# tm7_revC.net
KiCad netlist of a schematic drawn in EAGLE
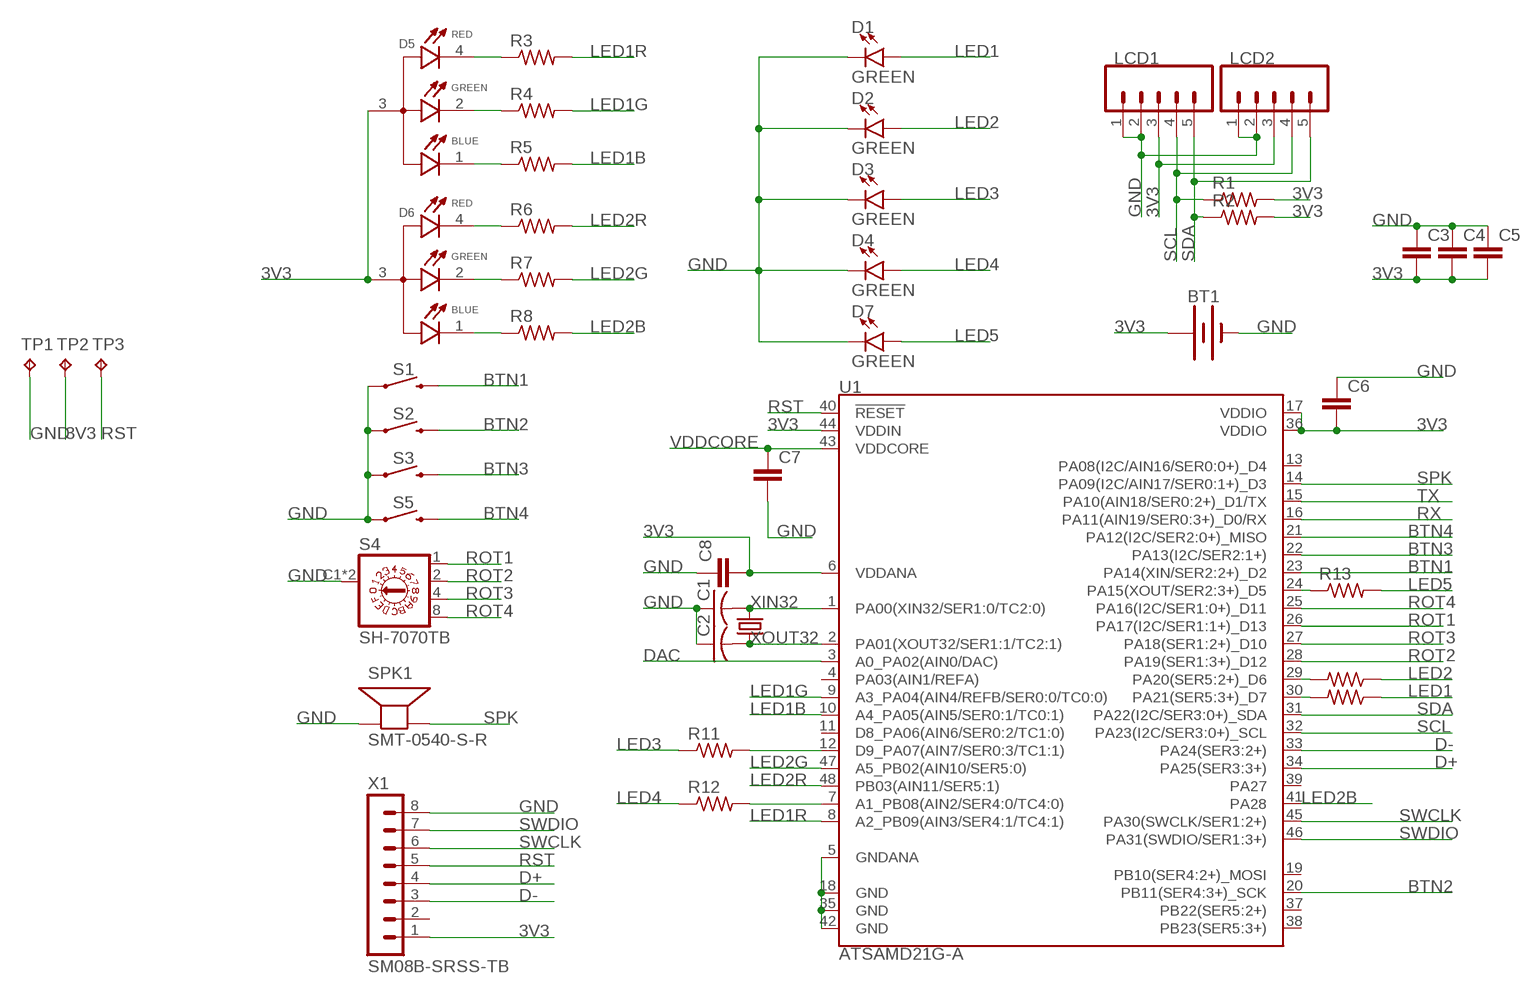
[diagram p0: schematic, sheet 1]

(export (version "E")
  (design (tool "Eeschema 10.0.6"))
  (components
    (comp (ref "BT1")
      (value "BATTERY-20MM_SMD_4LEGS_OVERPASTE_INNER")
      (footprint "eagle-import:BATTCON_20MM_4LEGS_OVERPASTE_INNER")
      (libsource (lib "eagle-import") (part "BATTERY-20MM_SMD_4LEGS_OVERPASTE_INNER"))
    )
    (comp (ref "C1")
      (value "C-USC0603")
      (footprint "eagle-import:C0603")
      (libsource (lib "eagle-import") (part "C-USC0603"))
    )
    (comp (ref "C2")
      (value "C-USC0603")
      (footprint "eagle-import:C0603")
      (libsource (lib "eagle-import") (part "C-USC0603"))
    )
    (comp (ref "C3")
      (value "C-EUC0603")
      (footprint "eagle-import:C0603")
      (libsource (lib "eagle-import") (part "C-EUC0603"))
    )
    (comp (ref "C4")
      (value "C-EUC0603")
      (footprint "eagle-import:C0603")
      (libsource (lib "eagle-import") (part "C-EUC0603"))
    )
    (comp (ref "C5")
      (value "C-EUC0603")
      (footprint "eagle-import:C0603")
      (libsource (lib "eagle-import") (part "C-EUC0603"))
    )
    (comp (ref "C6")
      (value "C-EUC0603")
      (footprint "eagle-import:C0603")
      (libsource (lib "eagle-import") (part "C-EUC0603"))
    )
    (comp (ref "C7")
      (value "C-EUC0603")
      (footprint "eagle-import:C0603")
      (libsource (lib "eagle-import") (part "C-EUC0603"))
    )
    (comp (ref "C8")
      (value "C-EUC0603")
      (footprint "eagle-import:C0603")
      (libsource (lib "eagle-import") (part "C-EUC0603"))
    )
    (comp (ref "D1")
      (value "GREEN")
      (footprint "eagle-import:LED-1206")
      (libsource (lib "eagle-import") (part "LED-GREEN1206"))
    )
    (comp (ref "D2")
      (value "GREEN")
      (footprint "eagle-import:LED-1206")
      (libsource (lib "eagle-import") (part "LED-GREEN1206"))
    )
    (comp (ref "D3")
      (value "GREEN")
      (footprint "eagle-import:LED-1206")
      (libsource (lib "eagle-import") (part "LED-GREEN1206"))
    )
    (comp (ref "D4")
      (value "GREEN")
      (footprint "eagle-import:LED-1206")
      (libsource (lib "eagle-import") (part "LED-GREEN1206"))
    )
    (comp (ref "D5")
      (value "EAST1616RGBA3")
      (footprint "eagle-import:LED_EAST1616RGBA3")
      (fields (field (name "MF") "Everlight Electronics"))
      (libsource (lib "eagle-import") (part "EAST1616RGBA3"))
    )
    (comp (ref "D6")
      (value "EAST1616RGBA3")
      (footprint "eagle-import:LED_EAST1616RGBA3")
      (fields (field (name "MF") "Everlight Electronics"))
      (libsource (lib "eagle-import") (part "EAST1616RGBA3"))
    )
    (comp (ref "D7")
      (value "GREEN")
      (footprint "eagle-import:LED-1206")
      (libsource (lib "eagle-import") (part "LED-GREEN1206"))
    )
    (comp (ref "LCD1")
      (value "CONN_05VERT_FEMALE_HEADER")
      (footprint "eagle-import:1X05_SMD_VERTICAL_COMBO")
      (libsource (lib "eagle-import") (part "CONN_05VERT_FEMALE_HEADER"))
    )
    (comp (ref "LCD2")
      (value "CONN_05VERT_FEMALE_HEADER")
      (footprint "eagle-import:1X05_SMD_VERTICAL_COMBO")
      (libsource (lib "eagle-import") (part "CONN_05VERT_FEMALE_HEADER"))
    )
    (comp (ref "R1")
      (value "R-US_R0603")
      (footprint "eagle-import:R0603")
      (libsource (lib "eagle-import") (part "R-US_R0603"))
    )
    (comp (ref "R2")
      (value "R-US_R0603")
      (footprint "eagle-import:R0603")
      (libsource (lib "eagle-import") (part "R-US_R0603"))
    )
    (comp (ref "R3")
      (value "R-US_R0603")
      (footprint "eagle-import:R0603")
      (libsource (lib "eagle-import") (part "R-US_R0603"))
    )
    (comp (ref "R4")
      (value "R-US_R0603")
      (footprint "eagle-import:R0603")
      (libsource (lib "eagle-import") (part "R-US_R0603"))
    )
    (comp (ref "R5")
      (value "R-US_R0603")
      (footprint "eagle-import:R0603")
      (libsource (lib "eagle-import") (part "R-US_R0603"))
    )
    (comp (ref "R6")
      (value "R-US_R0603")
      (footprint "eagle-import:R0603")
      (libsource (lib "eagle-import") (part "R-US_R0603"))
    )
    (comp (ref "R7")
      (value "R-US_R0603")
      (footprint "eagle-import:R0603")
      (libsource (lib "eagle-import") (part "R-US_R0603"))
    )
    (comp (ref "R8")
      (value "R-US_R0603")
      (footprint "eagle-import:R0603")
      (libsource (lib "eagle-import") (part "R-US_R0603"))
    )
    (comp (ref "R9")
      (value "R-US_R0603")
      (footprint "eagle-import:R0603")
      (libsource (lib "eagle-import") (part "R-US_R0603"))
    )
    (comp (ref "R10")
      (value "R-US_R0603")
      (footprint "eagle-import:R0603")
      (libsource (lib "eagle-import") (part "R-US_R0603"))
    )
    (comp (ref "R11")
      (value "R-US_R0603")
      (footprint "eagle-import:R0603")
      (libsource (lib "eagle-import") (part "R-US_R0603"))
    )
    (comp (ref "R12")
      (value "R-US_R0603")
      (footprint "eagle-import:R0603")
      (libsource (lib "eagle-import") (part "R-US_R0603"))
    )
    (comp (ref "R13")
      (value "R-US_R0603")
      (footprint "eagle-import:R0603")
      (libsource (lib "eagle-import") (part "R-US_R0603"))
    )
    (comp (ref "S1")
      (value "MOMENTARY-SWITCH-SPST-SMD-6.0X3.5MM")
      (footprint "eagle-import:TACTILE_SWITCH_SMD_6.0X3.5MM")
      (libsource (lib "eagle-import") (part "MOMENTARY-SWITCH-SPST-SMD-6.0X3.5MM"))
    )
    (comp (ref "S2")
      (value "MOMENTARY-SWITCH-SPST-SMD-6.0X3.5MM")
      (footprint "eagle-import:TACTILE_SWITCH_SMD_6.0X3.5MM")
      (libsource (lib "eagle-import") (part "MOMENTARY-SWITCH-SPST-SMD-6.0X3.5MM"))
    )
    (comp (ref "S3")
      (value "MOMENTARY-SWITCH-SPST-SMD-6.0X3.5MM")
      (footprint "eagle-import:TACTILE_SWITCH_SMD_6.0X3.5MM")
      (libsource (lib "eagle-import") (part "MOMENTARY-SWITCH-SPST-SMD-6.0X3.5MM"))
    )
    (comp (ref "S4")
      (value "SH-7070TB")
      (footprint "eagle-import:SH-7070B")
      (fields (field (name "MF") "Nidec Copal"))
      (libsource (lib "eagle-import") (part "SH-7070TB"))
    )
    (comp (ref "S5")
      (value "MOMENTARY-SWITCH-SPST-SMD-6.0X3.5MM")
      (footprint "eagle-import:TACTILE_SWITCH_SMD_6.0X3.5MM")
      (libsource (lib "eagle-import") (part "MOMENTARY-SWITCH-SPST-SMD-6.0X3.5MM"))
    )
    (comp (ref "SPK1")
      (value "SMT-0540-S-R")
      (footprint "eagle-import:SMT-0540-S-R")
      (fields (field (name "MF") "PUI"))
      (libsource (lib "eagle-import") (part "SMT-0540-S-R"))
    )
    (comp (ref "TP1")
      (value "TPTP12R")
      (footprint "eagle-import:TP12R")
      (libsource (lib "eagle-import") (part "TPTP12R"))
    )
    (comp (ref "TP2")
      (value "TPTP12R")
      (footprint "eagle-import:TP12R")
      (libsource (lib "eagle-import") (part "TPTP12R"))
    )
    (comp (ref "TP3")
      (value "TPTP12R")
      (footprint "eagle-import:TP12R")
      (libsource (lib "eagle-import") (part "TPTP12R"))
    )
    (comp (ref "U1")
      (value "ATSAMD21G-A")
      (footprint "eagle-import:TQFP-48")
      (libsource (lib "eagle-import") (part "ATSAMD21G-A"))
    )
    (comp (ref "X1")
      (value "SM08B-SRSS-TB")
      (footprint "eagle-import:SM08B-SRSS-TB")
      (libsource (lib "eagle-import") (part "SM08B-SRSS-TB"))
    )
    (comp (ref "Y1")
      (value "32.768kHz")
      (footprint "eagle-import:CRYSTAL-SMD-3.2X1.5MM")
      (libsource (lib "eagle-import") (part "CRYSTAL-32.768KHZSMD-3.2X1.5"))
    )
  )
  (nets
    (net (code "1") (name "/3V3") (class "Default")
      (node (ref "BT1") (pin "1") (pinfunction "+_1") (pintype "power_in"))
      (node (ref "C3") (pin "2") (pinfunction "2_2") (pintype "passive"))
      (node (ref "C4") (pin "2") (pinfunction "2_2") (pintype "passive"))
      (node (ref "C5") (pin "2") (pinfunction "2_2") (pintype "passive"))
      (node (ref "C6") (pin "2") (pinfunction "2_2") (pintype "passive"))
      (node (ref "C8") (pin "2") (pinfunction "2_2") (pintype "passive"))
      (node (ref "D5") (pin "3") (pinfunction "A_3") (pintype "passive"))
      (node (ref "D6") (pin "3") (pinfunction "A_3") (pintype "passive"))
      (node (ref "LCD1") (pin "3") (pinfunction "3_3") (pintype "passive"))
      (node (ref "LCD2") (pin "3") (pinfunction "3_3") (pintype "passive"))
      (node (ref "R1") (pin "2") (pinfunction "2_2") (pintype "passive"))
      (node (ref "R2") (pin "2") (pinfunction "2_2") (pintype "passive"))
      (node (ref "TP2") (pin "TP") (pinfunction "TP_TP") (pintype "input"))
      (node (ref "U1") (pin "17") (pinfunction "VDDIO_17") (pintype "bidirectional"))
      (node (ref "U1") (pin "36") (pinfunction "VDDIO_36") (pintype "bidirectional"))
      (node (ref "U1") (pin "44") (pinfunction "VDDIN_44") (pintype "bidirectional"))
      (node (ref "U1") (pin "6") (pinfunction "VDDANA_6") (pintype "bidirectional"))
      (node (ref "X1") (pin "1") (pinfunction "1_1") (pintype "passive"))
    )
    (net (code "2") (name "/BTN1") (class "Default")
      (node (ref "S1") (pin "2") (pinfunction "2_2") (pintype "passive"))
      (node (ref "U1") (pin "23") (pinfunction "PA14(XIN/SER2:2+)_D2_23") (pintype "bidirectional"))
    )
    (net (code "3") (name "/BTN2") (class "Default")
      (node (ref "S2") (pin "2") (pinfunction "2_2") (pintype "passive"))
      (node (ref "U1") (pin "20") (pinfunction "PB11(SER4:3+)_SCK_20") (pintype "bidirectional"))
    )
    (net (code "4") (name "/BTN3") (class "Default")
      (node (ref "S3") (pin "2") (pinfunction "2_2") (pintype "passive"))
      (node (ref "U1") (pin "22") (pinfunction "PA13(I2C/SER2:1+)_22") (pintype "bidirectional"))
    )
    (net (code "5") (name "/BTN4") (class "Default")
      (node (ref "S5") (pin "2") (pinfunction "2_2") (pintype "passive"))
      (node (ref "U1") (pin "21") (pinfunction "PA12(I2C/SER2:0+)_MISO_21") (pintype "bidirectional"))
    )
    (net (code "6") (name "/D+") (class "Default")
      (node (ref "U1") (pin "34") (pinfunction "PA25(SER3:3+)_34") (pintype "bidirectional"))
      (node (ref "X1") (pin "4") (pinfunction "4_4") (pintype "passive"))
    )
    (net (code "7") (name "/D-") (class "Default")
      (node (ref "U1") (pin "33") (pinfunction "PA24(SER3:2+)_33") (pintype "bidirectional"))
      (node (ref "X1") (pin "3") (pinfunction "3_3") (pintype "passive"))
    )
    (net (code "8") (name "/DAC") (class "Default")
      (node (ref "U1") (pin "3") (pinfunction "A0_PA02(AIN0/DAC)_3") (pintype "bidirectional"))
    )
    (net (code "9") (name "/GND") (class "Default")
      (node (ref "BT1") (pin "2") (pinfunction "-_2") (pintype "power_in"))
      (node (ref "C1") (pin "1") (pinfunction "1_1") (pintype "passive"))
      (node (ref "C2") (pin "1") (pinfunction "1_1") (pintype "passive"))
      (node (ref "C3") (pin "1") (pinfunction "1_1") (pintype "passive"))
      (node (ref "C4") (pin "1") (pinfunction "1_1") (pintype "passive"))
      (node (ref "C5") (pin "1") (pinfunction "1_1") (pintype "passive"))
      (node (ref "C6") (pin "1") (pinfunction "1_1") (pintype "passive"))
      (node (ref "C7") (pin "2") (pinfunction "2_2") (pintype "passive"))
      (node (ref "C8") (pin "1") (pinfunction "1_1") (pintype "passive"))
      (node (ref "D1") (pin "C") (pinfunction "C_C") (pintype "passive"))
      (node (ref "D2") (pin "C") (pinfunction "C_C") (pintype "passive"))
      (node (ref "D3") (pin "C") (pinfunction "C_C") (pintype "passive"))
      (node (ref "D4") (pin "C") (pinfunction "C_C") (pintype "passive"))
      (node (ref "D7") (pin "C") (pinfunction "C_C") (pintype "passive"))
      (node (ref "LCD1") (pin "1") (pinfunction "1_1") (pintype "passive"))
      (node (ref "LCD1") (pin "2") (pinfunction "2_2") (pintype "passive"))
      (node (ref "LCD2") (pin "1") (pinfunction "1_1") (pintype "passive"))
      (node (ref "LCD2") (pin "2") (pinfunction "2_2") (pintype "passive"))
      (node (ref "S1") (pin "1") (pinfunction "1_1") (pintype "passive"))
      (node (ref "S2") (pin "1") (pinfunction "1_1") (pintype "passive"))
      (node (ref "S3") (pin "1") (pinfunction "1_1") (pintype "passive"))
      (node (ref "S4") (pin "C1") (pinfunction "C_C1") (pintype "passive"))
      (node (ref "S4") (pin "C2") (pinfunction "C_C2") (pintype "passive"))
      (node (ref "S5") (pin "1") (pinfunction "1_1") (pintype "passive"))
      (node (ref "SPK1") (pin "-") (pinfunction "+_-") (pintype "passive"))
      (node (ref "TP1") (pin "TP") (pinfunction "TP_TP") (pintype "input"))
      (node (ref "U1") (pin "18") (pinfunction "GND_18") (pintype "bidirectional"))
      (node (ref "U1") (pin "35") (pinfunction "GND_35") (pintype "bidirectional"))
      (node (ref "U1") (pin "42") (pinfunction "GND_42") (pintype "bidirectional"))
      (node (ref "U1") (pin "5") (pinfunction "GNDANA_5") (pintype "bidirectional"))
      (node (ref "X1") (pin "8") (pinfunction "8_8") (pintype "passive"))
    )
    (net (code "10") (name "/LED1") (class "Default")
      (node (ref "D1") (pin "A") (pinfunction "A_A") (pintype "passive"))
      (node (ref "R9") (pin "1") (pinfunction "1_1") (pintype "passive"))
    )
    (net (code "11") (name "/LED1B") (class "Default")
      (node (ref "R5") (pin "2") (pinfunction "2_2") (pintype "passive"))
      (node (ref "U1") (pin "10") (pinfunction "A4_PA05(AIN5/SER0:1/TC0:1)_10") (pintype "bidirectional"))
    )
    (net (code "12") (name "/LED1G") (class "Default")
      (node (ref "R4") (pin "2") (pinfunction "2_2") (pintype "passive"))
      (node (ref "U1") (pin "9") (pinfunction "A3_PA04(AIN4/REFB/SER0:0/TC0:0)_9") (pintype "bidirectional"))
    )
    (net (code "13") (name "/LED1R") (class "Default")
      (node (ref "R3") (pin "2") (pinfunction "2_2") (pintype "passive"))
      (node (ref "U1") (pin "8") (pinfunction "A2_PB09(AIN3/SER4:1/TC4:1)_8") (pintype "bidirectional"))
    )
    (net (code "14") (name "/LED2") (class "Default")
      (node (ref "D2") (pin "A") (pinfunction "A_A") (pintype "passive"))
      (node (ref "R10") (pin "1") (pinfunction "1_1") (pintype "passive"))
    )
    (net (code "15") (name "/LED2B") (class "Default")
      (node (ref "R8") (pin "2") (pinfunction "2_2") (pintype "passive"))
      (node (ref "U1") (pin "41") (pinfunction "PA28_41") (pintype "bidirectional"))
    )
    (net (code "16") (name "/LED2G") (class "Default")
      (node (ref "R7") (pin "2") (pinfunction "2_2") (pintype "passive"))
      (node (ref "U1") (pin "47") (pinfunction "A5_PB02(AIN10/SER5:0)_47") (pintype "bidirectional"))
    )
    (net (code "17") (name "/LED2R") (class "Default")
      (node (ref "R6") (pin "2") (pinfunction "2_2") (pintype "passive"))
      (node (ref "U1") (pin "48") (pinfunction "PB03(AIN11/SER5:1)_48") (pintype "bidirectional"))
    )
    (net (code "18") (name "/LED3") (class "Default")
      (node (ref "D3") (pin "A") (pinfunction "A_A") (pintype "passive"))
      (node (ref "R11") (pin "1") (pinfunction "1_1") (pintype "passive"))
    )
    (net (code "19") (name "/LED4") (class "Default")
      (node (ref "D4") (pin "A") (pinfunction "A_A") (pintype "passive"))
      (node (ref "R12") (pin "1") (pinfunction "1_1") (pintype "passive"))
    )
    (net (code "20") (name "/LED5") (class "Default")
      (node (ref "D7") (pin "A") (pinfunction "A_A") (pintype "passive"))
      (node (ref "R13") (pin "2") (pinfunction "2_2") (pintype "passive"))
    )
    (net (code "21") (name "/ROT1") (class "Default")
      (node (ref "S4") (pin "1") (pinfunction "1_1") (pintype "passive"))
      (node (ref "U1") (pin "26") (pinfunction "PA17(I2C/SER1:1+)_D13_26") (pintype "bidirectional"))
    )
    (net (code "22") (name "/ROT2") (class "Default")
      (node (ref "S4") (pin "2") (pinfunction "2_2") (pintype "passive"))
      (node (ref "U1") (pin "28") (pinfunction "PA19(SER1:3+)_D12_28") (pintype "bidirectional"))
    )
    (net (code "23") (name "/ROT3") (class "Default")
      (node (ref "S4") (pin "4") (pinfunction "4_4") (pintype "passive"))
      (node (ref "U1") (pin "27") (pinfunction "PA18(SER1:2+)_D10_27") (pintype "bidirectional"))
    )
    (net (code "24") (name "/ROT4") (class "Default")
      (node (ref "S4") (pin "8") (pinfunction "8_8") (pintype "passive"))
      (node (ref "U1") (pin "25") (pinfunction "PA16(I2C/SER1:0+)_D11_25") (pintype "bidirectional"))
    )
    (net (code "25") (name "/RST") (class "Default")
      (node (ref "TP3") (pin "TP") (pinfunction "TP_TP") (pintype "input"))
      (node (ref "U1") (pin "40") (pinfunction "~{RESET}_40") (pintype "bidirectional"))
      (node (ref "X1") (pin "5") (pinfunction "5_5") (pintype "passive"))
    )
    (net (code "26") (name "/RX") (class "Default")
      (node (ref "U1") (pin "16") (pinfunction "PA11(AIN19/SER0:3+)_D0/RX_16") (pintype "bidirectional"))
    )
    (net (code "27") (name "/SCL") (class "Default")
      (node (ref "LCD1") (pin "4") (pinfunction "4_4") (pintype "passive"))
      (node (ref "LCD2") (pin "4") (pinfunction "4_4") (pintype "passive"))
      (node (ref "R1") (pin "1") (pinfunction "1_1") (pintype "passive"))
      (node (ref "U1") (pin "32") (pinfunction "PA23(I2C/SER3:0+)_SCL_32") (pintype "bidirectional"))
    )
    (net (code "28") (name "/SDA") (class "Default")
      (node (ref "LCD1") (pin "5") (pinfunction "5_5") (pintype "passive"))
      (node (ref "LCD2") (pin "5") (pinfunction "5_5") (pintype "passive"))
      (node (ref "R2") (pin "1") (pinfunction "1_1") (pintype "passive"))
      (node (ref "U1") (pin "31") (pinfunction "PA22(I2C/SER3:0+)_SDA_31") (pintype "bidirectional"))
    )
    (net (code "29") (name "/SPK") (class "Default")
      (node (ref "SPK1") (pin "+") (pinfunction "-_+") (pintype "passive"))
      (node (ref "U1") (pin "14") (pinfunction "PA09(I2C/AIN17/SER0:1+)_D3_14") (pintype "bidirectional"))
    )
    (net (code "30") (name "/SWCLK") (class "Default")
      (node (ref "U1") (pin "45") (pinfunction "PA30(SWCLK/SER1:2+)_45") (pintype "bidirectional"))
      (node (ref "X1") (pin "6") (pinfunction "6_6") (pintype "passive"))
    )
    (net (code "31") (name "/SWDIO") (class "Default")
      (node (ref "U1") (pin "46") (pinfunction "PA31(SWDIO/SER1:3+)_46") (pintype "bidirectional"))
      (node (ref "X1") (pin "7") (pinfunction "7_7") (pintype "passive"))
    )
    (net (code "32") (name "/TX") (class "Default")
      (node (ref "U1") (pin "15") (pinfunction "PA10(AIN18/SER0:2+)_D1/TX_15") (pintype "bidirectional"))
    )
    (net (code "33") (name "/VDDCORE") (class "Default")
      (node (ref "C7") (pin "1") (pinfunction "1_1") (pintype "passive"))
      (node (ref "U1") (pin "43") (pinfunction "VDDCORE_43") (pintype "bidirectional"))
    )
    (net (code "34") (name "/XIN32") (class "Default")
      (node (ref "C1") (pin "2") (pinfunction "2_2") (pintype "passive"))
      (node (ref "U1") (pin "1") (pinfunction "PA00(XIN32/SER1:0/TC2:0)_1") (pintype "bidirectional"))
      (node (ref "Y1") (pin "P$2") (pinfunction "2_P$2") (pintype "passive"))
    )
    (net (code "35") (name "/XOUT32") (class "Default")
      (node (ref "C2") (pin "2") (pinfunction "2_2") (pintype "passive"))
      (node (ref "U1") (pin "2") (pinfunction "PA01(XOUT32/SER1:1/TC2:1)_2") (pintype "bidirectional"))
      (node (ref "Y1") (pin "P$1") (pinfunction "1_P$1") (pintype "passive"))
    )
    (net (code "36") (name "Net-(D5-B_C)") (class "Default")
      (node (ref "D5") (pin "1") (pinfunction "B_C_1") (pintype "passive"))
      (node (ref "R5") (pin "1") (pinfunction "1_1") (pintype "passive"))
    )
    (net (code "37") (name "Net-(D5-G_C)") (class "Default")
      (node (ref "D5") (pin "2") (pinfunction "G_C_2") (pintype "passive"))
      (node (ref "R4") (pin "1") (pinfunction "1_1") (pintype "passive"))
    )
    (net (code "38") (name "Net-(D5-R_C)") (class "Default")
      (node (ref "D5") (pin "4") (pinfunction "R_C_4") (pintype "passive"))
      (node (ref "R3") (pin "1") (pinfunction "1_1") (pintype "passive"))
    )
    (net (code "39") (name "Net-(D6-B_C)") (class "Default")
      (node (ref "D6") (pin "1") (pinfunction "B_C_1") (pintype "passive"))
      (node (ref "R8") (pin "1") (pinfunction "1_1") (pintype "passive"))
    )
    (net (code "40") (name "Net-(D6-G_C)") (class "Default")
      (node (ref "D6") (pin "2") (pinfunction "G_C_2") (pintype "passive"))
      (node (ref "R7") (pin "1") (pinfunction "1_1") (pintype "passive"))
    )
    (net (code "41") (name "Net-(D6-R_C)") (class "Default")
      (node (ref "D6") (pin "4") (pinfunction "R_C_4") (pintype "passive"))
      (node (ref "R6") (pin "1") (pinfunction "1_1") (pintype "passive"))
    )
    (net (code "42") (name "Net-(U1-A1_PB08(AIN2{slash}SER4:0{slash}TC4:0))") (class "Default")
      (node (ref "R12") (pin "2") (pinfunction "2_2") (pintype "passive"))
      (node (ref "U1") (pin "7") (pinfunction "A1_PB08(AIN2/SER4:0/TC4:0)_7") (pintype "bidirectional"))
    )
    (net (code "43") (name "Net-(U1-D9_PA07(AIN7{slash}SER0:3{slash}TC1:1))") (class "Default")
      (node (ref "R11") (pin "2") (pinfunction "2_2") (pintype "passive"))
      (node (ref "U1") (pin "12") (pinfunction "D9_PA07(AIN7/SER0:3/TC1:1)_12") (pintype "bidirectional"))
    )
    (net (code "44") (name "Net-(U1-PA15(XOUT{slash}SER2:3+)_D5)") (class "Default")
      (node (ref "R13") (pin "1") (pinfunction "1_1") (pintype "passive"))
      (node (ref "U1") (pin "24") (pinfunction "PA15(XOUT/SER2:3+)_D5_24") (pintype "bidirectional"))
    )
    (net (code "45") (name "Net-(U1-PA20(SER5:2+)_D6)") (class "Default")
      (node (ref "R10") (pin "2") (pinfunction "2_2") (pintype "passive"))
      (node (ref "U1") (pin "29") (pinfunction "PA20(SER5:2+)_D6_29") (pintype "bidirectional"))
    )
    (net (code "46") (name "Net-(U1-PA21(SER5:3+)_D7)") (class "Default")
      (node (ref "R9") (pin "2") (pinfunction "2_2") (pintype "passive"))
      (node (ref "U1") (pin "30") (pinfunction "PA21(SER5:3+)_D7_30") (pintype "bidirectional"))
    )
    (net (code "47") (name "unconnected-(U1-D8_PA06(AIN6{slash}SER0:2{slash}TC1:0)-Pad11)") (class "Default")
      (node (ref "U1") (pin "11") (pinfunction "D8_PA06(AIN6/SER0:2/TC1:0)_11") (pintype "bidirectional"))
    )
    (net (code "48") (name "unconnected-(U1-PA03(AIN1{slash}REFA)-Pad4)") (class "Default")
      (node (ref "U1") (pin "4") (pinfunction "PA03(AIN1/REFA)_4") (pintype "bidirectional"))
    )
    (net (code "49") (name "unconnected-(U1-PA08(I2C{slash}AIN16{slash}SER0:0+)_D4-Pad13)") (class "Default")
      (node (ref "U1") (pin "13") (pinfunction "PA08(I2C/AIN16/SER0:0+)_D4_13") (pintype "bidirectional"))
    )
    (net (code "50") (name "unconnected-(U1-PA27-Pad39)") (class "Default")
      (node (ref "U1") (pin "39") (pinfunction "PA27_39") (pintype "bidirectional"))
    )
    (net (code "51") (name "unconnected-(U1-PB10(SER4:2+)_MOSI-Pad19)") (class "Default")
      (node (ref "U1") (pin "19") (pinfunction "PB10(SER4:2+)_MOSI_19") (pintype "bidirectional"))
    )
    (net (code "52") (name "unconnected-(U1-PB22(SER5:2+)-Pad37)") (class "Default")
      (node (ref "U1") (pin "37") (pinfunction "PB22(SER5:2+)_37") (pintype "bidirectional"))
    )
    (net (code "53") (name "unconnected-(U1-PB23(SER5:3+)-Pad38)") (class "Default")
      (node (ref "U1") (pin "38") (pinfunction "PB23(SER5:3+)_38") (pintype "bidirectional"))
    )
    (net (code "54") (name "unconnected-(X1-Pad2)") (class "Default")
      (node (ref "X1") (pin "2") (pinfunction "2_2") (pintype "passive"))
    )
  )
)
